# TP4056.net
KiCad netlist of a schematic drawn in Altium Designer
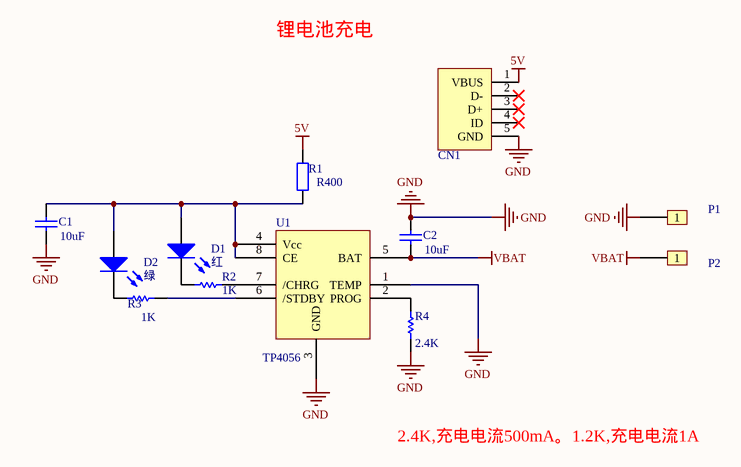
[diagram p0: TP4056电源模块.SchDoc]

(export (version "E")
  (design (tool "Eeschema 10.0.6"))
  (components
    (comp (ref "C1")
      (value "10uF")
      (footprint "0603C")
      (description "Capacitor")
      (fields (field (name "Comment") "Cap") (field (name "PUBLISHER") "Altium Limited"))
      (libsource (lib "Miscellaneous Devices") (part "Cap"))
    )
    (comp (ref "C2")
      (value "10uF")
      (footprint "0603C")
      (description "Capacitor")
      (fields (field (name "Comment") "Cap") (field (name "PUBLISHER") "Altium Limited"))
      (libsource (lib "Miscellaneous Devices") (part "Cap"))
    )
    (comp (ref "CN1")
      (value "microUSB")
      (footprint "MICRO-USB")
      (libsource (lib "Zachary") (part "USB_micro"))
    )
    (comp (ref "D1")
      (value "红")
      (footprint "0805D")
      (description "Typical INFRARED GaAs LED")
      (fields (field (name "PUBLISHER") "Altium Limited"))
      (libsource (lib "Miscellaneous Devices") (part "LED0"))
    )
    (comp (ref "D2")
      (value "绿")
      (footprint "0805D")
      (description "Typical INFRARED GaAs LED")
      (fields (field (name "PUBLISHER") "Altium Limited"))
      (libsource (lib "Miscellaneous Devices") (part "LED0"))
    )
    (comp (ref "P1") (value "Header1") (footprint "Header1") (libsource (lib "Zachary") (part "Header1")))
    (comp (ref "P2") (value "Header1") (footprint "Header1") (libsource (lib "Zachary") (part "Header1")))
    (comp (ref "R1")
      (value "R400")
      (footprint "1206R")
      (description "Resistor")
      (fields (field (name "Comment") "Res2") (field (name "PUBLISHER") "Altium Limited"))
      (libsource (lib "Miscellaneous Devices") (part "Res2"))
    )
    (comp (ref "R2")
      (value "1K")
      (footprint "0603R")
      (description "Resistor")
      (fields (field (name "Comment") "Res1") (field (name "PUBLISHER") "Altium Limited"))
      (libsource (lib "Miscellaneous Devices") (part "Res1"))
    )
    (comp (ref "R3")
      (value "1K")
      (footprint "0603R")
      (description "Resistor")
      (fields (field (name "Comment") "Res1") (field (name "PUBLISHER") "Altium Limited"))
      (libsource (lib "Miscellaneous Devices") (part "Res1"))
    )
    (comp (ref "R4")
      (value "2.4K")
      (footprint "0603R")
      (description "Resistor")
      (fields (field (name "Comment") "Res1") (field (name "PUBLISHER") "Altium Limited"))
      (libsource (lib "Miscellaneous Devices") (part "Res1"))
    )
    (comp (ref "U1") (value "TP4056") (footprint "SOP-8") (libsource (lib "Zachary") (part "TP4056")))
  )
  (nets
    (net (code "1") (name "5V") (class "Default")
      (node (ref "CN1") (pin "1") (pinfunction "VBUS_1") (pintype "passive"))
      (node (ref "R1") (pin "2") (pinfunction "2_2") (pintype "passive"))
    )
    (net (code "2") (name "GND") (class "Default")
      (node (ref "C1") (pin "1") (pinfunction "1_1") (pintype "passive"))
      (node (ref "C2") (pin "2") (pinfunction "2_2") (pintype "passive"))
      (node (ref "CN1") (pin "5") (pinfunction "GND_5") (pintype "passive"))
      (node (ref "P1") (pin "1") (pinfunction "1_1") (pintype "passive"))
      (node (ref "R4") (pin "1") (pinfunction "1_1") (pintype "passive"))
      (node (ref "U1") (pin "1") (pinfunction "TEMP_1") (pintype "passive"))
      (node (ref "U1") (pin "3") (pinfunction "GND_3") (pintype "passive"))
    )
    (net (code "3") (name "Net-(D1-A)") (class "Default")
      (node (ref "C1") (pin "2") (pinfunction "2_2") (pintype "passive"))
      (node (ref "D1") (pin "1") (pinfunction "A_1") (pintype "passive"))
      (node (ref "D2") (pin "1") (pinfunction "A_1") (pintype "passive"))
      (node (ref "R1") (pin "1") (pinfunction "1_1") (pintype "passive"))
      (node (ref "U1") (pin "4") (pinfunction "Vcc_4") (pintype "passive"))
      (node (ref "U1") (pin "8") (pinfunction "CE_8") (pintype "passive"))
    )
    (net (code "4") (name "Net-(D1-K)") (class "Default")
      (node (ref "D1") (pin "2") (pinfunction "K_2") (pintype "passive"))
      (node (ref "R2") (pin "1") (pinfunction "1_1") (pintype "passive"))
    )
    (net (code "5") (name "Net-(D2-K)") (class "Default")
      (node (ref "D2") (pin "2") (pinfunction "K_2") (pintype "passive"))
      (node (ref "R3") (pin "1") (pinfunction "1_1") (pintype "passive"))
    )
    (net (code "6") (name "Net-(U1-PROG)") (class "Default")
      (node (ref "R4") (pin "2") (pinfunction "2_2") (pintype "passive"))
      (node (ref "U1") (pin "2") (pinfunction "PROG_2") (pintype "passive"))
    )
    (net (code "7") (name "Net-(U1-{slash}CHRG)") (class "Default")
      (node (ref "R2") (pin "2") (pinfunction "2_2") (pintype "passive"))
      (node (ref "U1") (pin "7") (pinfunction "/CHRG_7") (pintype "passive"))
    )
    (net (code "8") (name "Net-(U1-{slash}STDBY)") (class "Default")
      (node (ref "R3") (pin "2") (pinfunction "2_2") (pintype "passive"))
      (node (ref "U1") (pin "6") (pinfunction "/STDBY_6") (pintype "passive"))
    )
    (net (code "9") (name "VBAT") (class "Default")
      (node (ref "C2") (pin "1") (pinfunction "1_1") (pintype "passive"))
      (node (ref "P2") (pin "1") (pinfunction "1_1") (pintype "passive"))
      (node (ref "U1") (pin "5") (pinfunction "BAT_5") (pintype "passive"))
    )
    (net (code "10") (name "unconnected-(CN1-D+-Pad3)") (class "Default")
      (node (ref "CN1") (pin "3") (pinfunction "D+_3") (pintype "passive+no_connect"))
    )
    (net (code "11") (name "unconnected-(CN1-D--Pad2)") (class "Default")
      (node (ref "CN1") (pin "2") (pinfunction "D-_2") (pintype "passive+no_connect"))
    )
    (net (code "12") (name "unconnected-(CN1-ID-Pad4)") (class "Default")
      (node (ref "CN1") (pin "4") (pinfunction "ID_4") (pintype "passive+no_connect"))
    )
  )
)
